# USB_Protection.net
KiCad netlist of a schematic drawn in Altium Designer
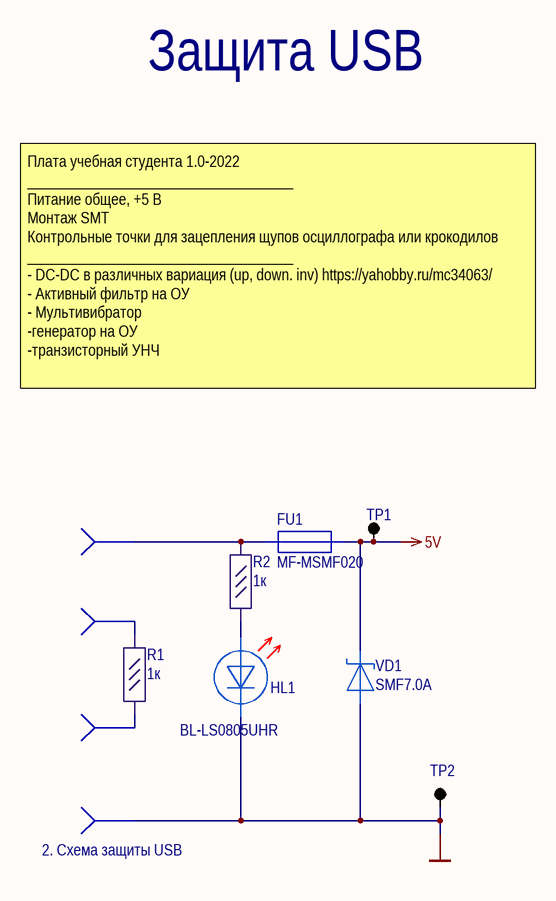
[diagram p0: USB_Protection.SchDoc]

(export (version "E")
  (design (tool "Eeschema 10.0.6"))
  (components
    (comp (ref "FU1")
      (value "MF-MSMF020")
      (footprint "11.Other:FUSE 1812")
      (libsource (lib "11.Other") (part "MF-MSMF020"))
    )
    (comp (ref "HL1")
      (value "BL-LS0805UHR")
      (footprint "LED_0805_RED")
      (libsource (lib "4.Diodes") (part "BL-LS0805UHR"))
    )
    (comp (ref "R1")
      (value "1к")
      (footprint "1.Resistors:R_0805")
      (description "RES SMD 10K OHM 1% 1/10W 0603")
      (fields (field (name "PART NUMBER") "CR0603-FX-1002ELF") (field (name "MANUFACTURER") "Bourns Inc."))
      (libsource (lib "Database_Lib") (part "Resistor"))
    )
    (comp (ref "R2")
      (value "1к")
      (footprint "1.Resistors:R_0805")
      (description "RES SMD 10K OHM 1% 1/10W 0603")
      (fields (field (name "PART NUMBER") "CR0603-FX-1002ELF") (field (name "MANUFACTURER") "Bourns Inc."))
      (libsource (lib "Database_Lib") (part "Resistor"))
    )
    (comp (ref "TP1")
      (value "Test_Point_1")
      (footprint "User_Library:PLS-1")
      (libsource (lib "7.Connectors") (part "Test_Point_1"))
    )
    (comp (ref "TP2")
      (value "Test_Point_1")
      (footprint "User_Library:PLS-1")
      (libsource (lib "7.Connectors") (part "Test_Point_1"))
    )
    (comp (ref "VD1")
      (value "SMF7.0A")
      (footprint "4.Diodes:SOD-123F")
      (description "Защитный диод, однонаправленный")
      (libsource (lib "4.Diodes") (part "SMAJ5.0A-TR"))
    )
    (comp (ref "X1")
      (value "X")
      (footprint "KT_1")
      (description "Контактная площадка")
      (libsource (lib "7.Connectors") (part "X"))
    )
    (comp (ref "X2")
      (value "X")
      (footprint "KT_1")
      (description "Контактная площадка")
      (libsource (lib "7.Connectors") (part "X"))
    )
    (comp (ref "X3")
      (value "X")
      (footprint "KT_1")
      (description "Контактная площадка")
      (libsource (lib "7.Connectors") (part "X"))
    )
    (comp (ref "X4")
      (value "X")
      (footprint "KT_1")
      (description "Контактная площадка")
      (libsource (lib "7.Connectors") (part "X"))
    )
  )
  (nets
    (net (code "1") (name "5V") (class "Default")
      (node (ref "FU1") (pin "2") (pinfunction "2_2") (pintype "passive"))
      (node (ref "TP1") (pin "1") (pinfunction "1_1") (pintype "passive"))
      (node (ref "VD1") (pin "2") (pinfunction "2_2") (pintype "passive"))
    )
    (net (code "2") (name "GND") (class "Default")
      (node (ref "HL1") (pin "2") (pinfunction "2_2") (pintype "passive"))
      (node (ref "TP2") (pin "1") (pinfunction "1_1") (pintype "passive"))
      (node (ref "VD1") (pin "1") (pinfunction "1_1") (pintype "passive"))
      (node (ref "X4") (pin "1") (pinfunction "1_1") (pintype "passive"))
    )
    (net (code "3") (name "Net-(FU1-Pad1)") (class "Default")
      (node (ref "FU1") (pin "1") (pinfunction "1_1") (pintype "passive"))
      (node (ref "R2") (pin "1") (pinfunction "1_1") (pintype "passive"))
      (node (ref "X1") (pin "1") (pinfunction "1_1") (pintype "passive"))
    )
    (net (code "4") (name "Net-(HL1-Pad1)") (class "Default")
      (node (ref "HL1") (pin "1") (pinfunction "1_1") (pintype "passive"))
      (node (ref "R2") (pin "2") (pinfunction "2_2") (pintype "passive"))
    )
    (net (code "5") (name "Net-(R1-Pad1)") (class "Default")
      (node (ref "R1") (pin "1") (pinfunction "1_1") (pintype "passive"))
      (node (ref "X2") (pin "1") (pinfunction "1_1") (pintype "passive"))
    )
    (net (code "6") (name "Net-(R1-Pad2)") (class "Default")
      (node (ref "R1") (pin "2") (pinfunction "2_2") (pintype "passive"))
      (node (ref "X3") (pin "1") (pinfunction "1_1") (pintype "passive"))
    )
  )
)
